# combo.net
KiCad netlist of a schematic drawn in EAGLE
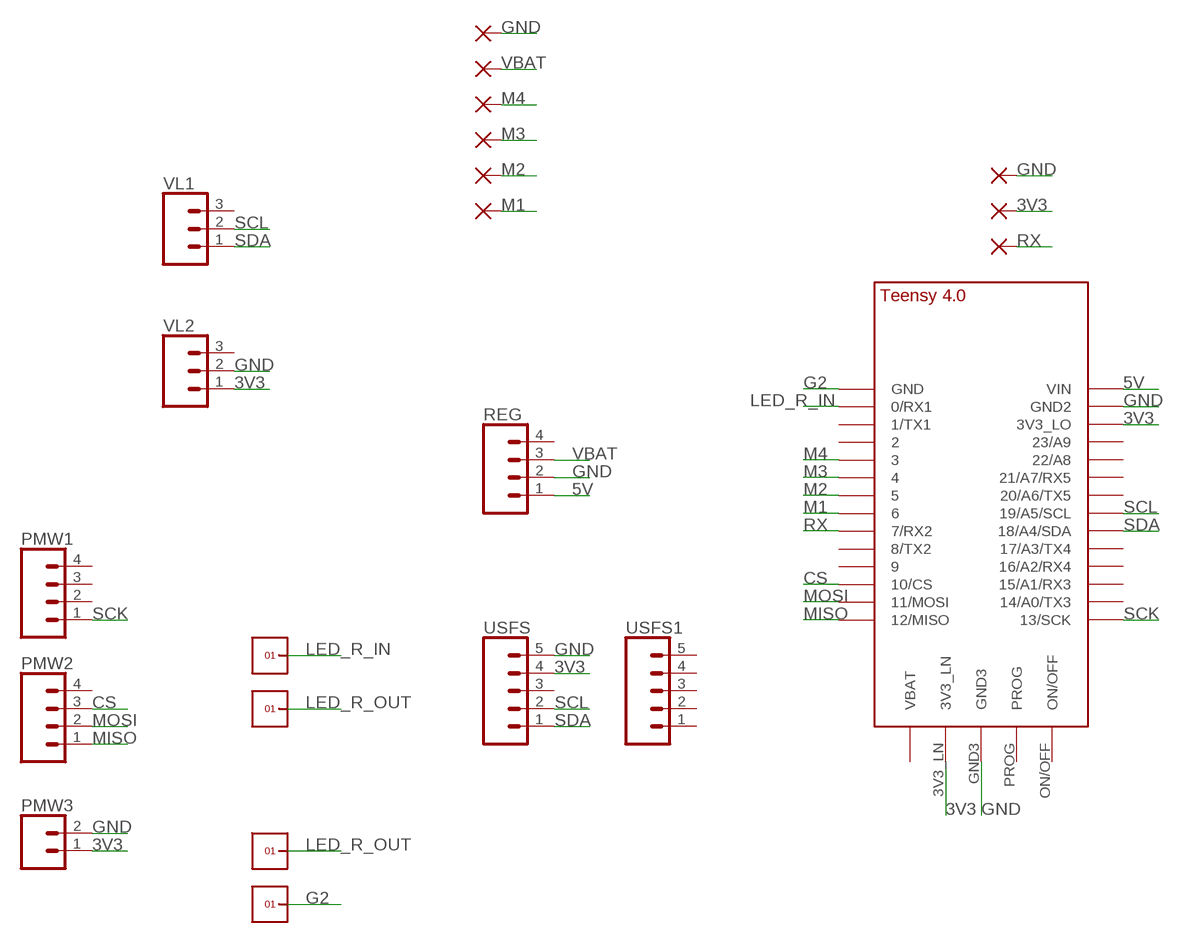
[diagram p0: schematic, sheet 1]

(export (version "E")
  (design (tool "Eeschema 10.0.6"))
  (components
    (comp (ref "3V")
      (value "SMD2")
      (footprint "eagle-import:SMD1,27-2,54")
      (libsource (lib "eagle-import") (part "SMD2"))
    )
    (comp (ref "GD")
      (value "SMD2")
      (footprint "eagle-import:SMD1,27-2,54")
      (libsource (lib "eagle-import") (part "SMD2"))
    )
    (comp (ref "GND")
      (value "SMD2")
      (footprint "eagle-import:SMD1,27-2,54")
      (libsource (lib "eagle-import") (part "SMD2"))
    )
    (comp (ref "M1")
      (value "SMD2")
      (footprint "eagle-import:SMD1,27-2,54")
      (libsource (lib "eagle-import") (part "SMD2"))
    )
    (comp (ref "M2")
      (value "SMD2")
      (footprint "eagle-import:SMD1,27-2,54")
      (libsource (lib "eagle-import") (part "SMD2"))
    )
    (comp (ref "M3")
      (value "SMD2")
      (footprint "eagle-import:SMD1,27-2,54")
      (libsource (lib "eagle-import") (part "SMD2"))
    )
    (comp (ref "M4")
      (value "SMD2")
      (footprint "eagle-import:SMD1,27-2,54")
      (libsource (lib "eagle-import") (part "SMD2"))
    )
    (comp (ref "PMW1")
      (value "CONN_041X04_NO_SILK")
      (footprint "eagle-import:1X04_NO_SILK")
      (libsource (lib "eagle-import") (part "CONN_041X04_NO_SILK"))
    )
    (comp (ref "PMW2")
      (value "CONN_041X04_NO_SILK")
      (footprint "eagle-import:1X04_NO_SILK")
      (libsource (lib "eagle-import") (part "CONN_041X04_NO_SILK"))
    )
    (comp (ref "PMW3")
      (value "CONN_021X02_NO_SILK")
      (footprint "eagle-import:1X02_NO_SILK")
      (libsource (lib "eagle-import") (part "CONN_021X02_NO_SILK"))
    )
    (comp (ref "REG")
      (value "CONN_041X04_NO_SILK")
      (footprint "eagle-import:1X04_NO_SILK")
      (libsource (lib "eagle-import") (part "CONN_041X04_NO_SILK"))
    )
    (comp (ref "RX")
      (value "SMD2")
      (footprint "eagle-import:SMD1,27-2,54")
      (libsource (lib "eagle-import") (part "SMD2"))
    )
    (comp (ref "U$1")
      (value "TEENSY_4.0")
      (footprint "eagle-import:TEENSY_4.0")
      (libsource (lib "eagle-import") (part "TEENSY_4.0"))
    )
    (comp (ref "U$3")
      (value "1X1")
      (footprint "eagle-import:1X1")
      (libsource (lib "eagle-import") (part "1X1"))
    )
    (comp (ref "U$4")
      (value "1X1")
      (footprint "eagle-import:1X1")
      (libsource (lib "eagle-import") (part "1X1"))
    )
    (comp (ref "U$6")
      (value "1X1")
      (footprint "eagle-import:1X1")
      (libsource (lib "eagle-import") (part "1X1"))
    )
    (comp (ref "U$7")
      (value "1X1")
      (footprint "eagle-import:1X1")
      (libsource (lib "eagle-import") (part "1X1"))
    )
    (comp (ref "USFS")
      (value "CONN_05NO_SILK")
      (footprint "eagle-import:1X05_NO_SILK")
      (libsource (lib "eagle-import") (part "CONN_05NO_SILK"))
    )
    (comp (ref "USFS1")
      (value "CONN_05NO_SILK")
      (footprint "eagle-import:1X05_NO_SILK")
      (libsource (lib "eagle-import") (part "CONN_05NO_SILK"))
    )
    (comp (ref "VBAT")
      (value "SMD2")
      (footprint "eagle-import:SMD1,27-2,54")
      (libsource (lib "eagle-import") (part "SMD2"))
    )
    (comp (ref "VL1")
      (value "CONN_031X03_NO_SILK")
      (footprint "eagle-import:1X03_NO_SILK")
      (libsource (lib "eagle-import") (part "CONN_031X03_NO_SILK"))
    )
    (comp (ref "VL2")
      (value "CONN_031X03_NO_SILK")
      (footprint "eagle-import:1X03_NO_SILK")
      (libsource (lib "eagle-import") (part "CONN_031X03_NO_SILK"))
    )
  )
  (nets
    (net (code "1") (name "/3V3") (class "Default")
      (node (ref "3V") (pin "1") (pinfunction "P_1") (pintype "passive"))
      (node (ref "PMW3") (pin "1") (pinfunction "1_1") (pintype "passive"))
      (node (ref "U$1") (pin "3V3_LN") (pinfunction "3V3_LN_3V3_LN") (pintype "bidirectional"))
      (node (ref "U$1") (pin "3V3_LO") (pinfunction "3V3_LO_3V3_LO") (pintype "bidirectional"))
      (node (ref "USFS") (pin "4") (pinfunction "4_4") (pintype "passive"))
      (node (ref "VL2") (pin "1") (pinfunction "1_1") (pintype "passive"))
    )
    (net (code "2") (name "/5V") (class "Default")
      (node (ref "REG") (pin "1") (pinfunction "1_1") (pintype "passive"))
      (node (ref "U$1") (pin "VIN") (pinfunction "VIN_VIN") (pintype "bidirectional"))
    )
    (net (code "3") (name "/CS") (class "Default")
      (node (ref "PMW2") (pin "3") (pinfunction "3_3") (pintype "passive"))
      (node (ref "U$1") (pin "10/CS") (pinfunction "10/CS_10/CS") (pintype "bidirectional"))
    )
    (net (code "4") (name "/G2") (class "Default")
      (node (ref "U$1") (pin "GND") (pinfunction "GND_GND") (pintype "bidirectional"))
      (node (ref "U$7") (pin "1") (pinfunction "1_1") (pintype "bidirectional"))
    )
    (net (code "5") (name "/GND") (class "Default")
      (node (ref "GD") (pin "1") (pinfunction "P_1") (pintype "passive"))
      (node (ref "GND") (pin "1") (pinfunction "P_1") (pintype "passive"))
      (node (ref "PMW3") (pin "2") (pinfunction "2_2") (pintype "passive"))
      (node (ref "REG") (pin "2") (pinfunction "2_2") (pintype "passive"))
      (node (ref "U$1") (pin "GND2") (pinfunction "GND2_GND2") (pintype "bidirectional"))
      (node (ref "U$1") (pin "GND3") (pinfunction "GND3_GND3") (pintype "bidirectional"))
      (node (ref "USFS") (pin "5") (pinfunction "5_5") (pintype "passive"))
      (node (ref "VL2") (pin "2") (pinfunction "2_2") (pintype "passive"))
    )
    (net (code "6") (name "/LED_R_IN") (class "Default")
      (node (ref "U$1") (pin "0/RX") (pinfunction "0/RX1_0/RX") (pintype "bidirectional"))
      (node (ref "U$3") (pin "1") (pinfunction "1_1") (pintype "bidirectional"))
    )
    (net (code "7") (name "/LED_R_OUT") (class "Default")
      (node (ref "U$4") (pin "1") (pinfunction "1_1") (pintype "bidirectional"))
      (node (ref "U$6") (pin "1") (pinfunction "1_1") (pintype "bidirectional"))
    )
    (net (code "8") (name "/M1") (class "Default")
      (node (ref "M1") (pin "1") (pinfunction "P_1") (pintype "passive"))
      (node (ref "U$1") (pin "6") (pinfunction "6_6") (pintype "bidirectional"))
    )
    (net (code "9") (name "/M2") (class "Default")
      (node (ref "M2") (pin "1") (pinfunction "P_1") (pintype "passive"))
      (node (ref "U$1") (pin "5") (pinfunction "5_5") (pintype "bidirectional"))
    )
    (net (code "10") (name "/M3") (class "Default")
      (node (ref "M3") (pin "1") (pinfunction "P_1") (pintype "passive"))
      (node (ref "U$1") (pin "4/CANRX") (pinfunction "4_4/CANRX") (pintype "bidirectional"))
    )
    (net (code "11") (name "/M4") (class "Default")
      (node (ref "M4") (pin "1") (pinfunction "P_1") (pintype "passive"))
      (node (ref "U$1") (pin "3/CANTX") (pinfunction "3_3/CANTX") (pintype "bidirectional"))
    )
    (net (code "12") (name "/MISO") (class "Default")
      (node (ref "PMW2") (pin "1") (pinfunction "1_1") (pintype "passive"))
      (node (ref "U$1") (pin "12/MISO") (pinfunction "12/MISO_12/MISO") (pintype "bidirectional"))
    )
    (net (code "13") (name "/MOSI") (class "Default")
      (node (ref "PMW2") (pin "2") (pinfunction "2_2") (pintype "passive"))
      (node (ref "U$1") (pin "11/MOSI") (pinfunction "11/MOSI_11/MOSI") (pintype "bidirectional"))
    )
    (net (code "14") (name "/RX") (class "Default")
      (node (ref "RX") (pin "1") (pinfunction "P_1") (pintype "passive"))
      (node (ref "U$1") (pin "7") (pinfunction "7/RX2_7") (pintype "bidirectional"))
    )
    (net (code "15") (name "/SCK") (class "Default")
      (node (ref "PMW1") (pin "1") (pinfunction "1_1") (pintype "passive"))
      (node (ref "U$1") (pin "13/SCK") (pinfunction "13/SCK_13/SCK") (pintype "bidirectional"))
    )
    (net (code "16") (name "/SCL") (class "Default")
      (node (ref "U$1") (pin "19/A5/SCL") (pinfunction "19/A5/SCL_19/A5/SCL") (pintype "bidirectional"))
      (node (ref "USFS") (pin "2") (pinfunction "2_2") (pintype "passive"))
      (node (ref "VL1") (pin "2") (pinfunction "2_2") (pintype "passive"))
    )
    (net (code "17") (name "/SDA") (class "Default")
      (node (ref "U$1") (pin "18/A4/SDA") (pinfunction "18/A4/SDA_18/A4/SDA") (pintype "bidirectional"))
      (node (ref "USFS") (pin "1") (pinfunction "1_1") (pintype "passive"))
      (node (ref "VL1") (pin "1") (pinfunction "1_1") (pintype "passive"))
    )
    (net (code "18") (name "/VBAT") (class "Default")
      (node (ref "REG") (pin "3") (pinfunction "3_3") (pintype "passive"))
      (node (ref "VBAT") (pin "1") (pinfunction "P_1") (pintype "passive"))
    )
    (net (code "19") (name "unconnected-(PMW1-Pad2)") (class "Default")
      (node (ref "PMW1") (pin "2") (pinfunction "2_2") (pintype "passive"))
    )
    (net (code "20") (name "unconnected-(PMW1-Pad3)") (class "Default")
      (node (ref "PMW1") (pin "3") (pinfunction "3_3") (pintype "passive"))
    )
    (net (code "21") (name "unconnected-(PMW1-Pad4)") (class "Default")
      (node (ref "PMW1") (pin "4") (pinfunction "4_4") (pintype "passive"))
    )
    (net (code "22") (name "unconnected-(PMW2-Pad4)") (class "Default")
      (node (ref "PMW2") (pin "4") (pinfunction "4_4") (pintype "passive"))
    )
    (net (code "23") (name "unconnected-(REG-Pad4)") (class "Default")
      (node (ref "REG") (pin "4") (pinfunction "4_4") (pintype "passive"))
    )
    (net (code "24") (name "unconnected-(U$1-1{slash}TX1-Pad1{slash}TX)") (class "Default")
      (node (ref "U$1") (pin "1/TX") (pinfunction "1/TX1_1/TX") (pintype "bidirectional"))
    )
    (net (code "25") (name "unconnected-(U$1-8{slash}TX2-Pad8)") (class "Default")
      (node (ref "U$1") (pin "8") (pinfunction "8/TX2_8") (pintype "bidirectional"))
    )
    (net (code "26") (name "unconnected-(U$1-9-Pad9{slash}CS)") (class "Default")
      (node (ref "U$1") (pin "9/CS") (pinfunction "9_9/CS") (pintype "bidirectional"))
    )
    (net (code "27") (name "unconnected-(U$1-14{slash}A0{slash}TX3-Pad14{slash}A0)") (class "Default")
      (node (ref "U$1") (pin "14/A0") (pinfunction "14/A0/TX3_14/A0") (pintype "bidirectional"))
    )
    (net (code "28") (name "unconnected-(U$1-15{slash}A1{slash}RX3-Pad15{slash}A1)") (class "Default")
      (node (ref "U$1") (pin "15/A1") (pinfunction "15/A1/RX3_15/A1") (pintype "bidirectional"))
    )
    (net (code "29") (name "unconnected-(U$1-16{slash}A2{slash}RX4-Pad16{slash}A2)") (class "Default")
      (node (ref "U$1") (pin "16/A2") (pinfunction "16/A2/RX4_16/A2") (pintype "bidirectional"))
    )
    (net (code "30") (name "unconnected-(U$1-17{slash}A3{slash}TX4-Pad17{slash}A3)") (class "Default")
      (node (ref "U$1") (pin "17/A3") (pinfunction "17/A3/TX4_17/A3") (pintype "bidirectional"))
    )
    (net (code "31") (name "unconnected-(U$1-20{slash}A6{slash}TX5-Pad20{slash}A6)") (class "Default")
      (node (ref "U$1") (pin "20/A6") (pinfunction "20/A6/TX5_20/A6") (pintype "bidirectional"))
    )
    (net (code "32") (name "unconnected-(U$1-21{slash}A7{slash}RX5-Pad21{slash}A7)") (class "Default")
      (node (ref "U$1") (pin "21/A7") (pinfunction "21/A7/RX5_21/A7") (pintype "bidirectional"))
    )
    (net (code "33") (name "unconnected-(U$1-Pad2)") (class "Default")
      (node (ref "U$1") (pin "2") (pinfunction "2_2") (pintype "bidirectional"))
    )
    (net (code "34") (name "unconnected-(U$1-Pad22{slash}A8)") (class "Default")
      (node (ref "U$1") (pin "22/A8") (pinfunction "22/A8_22/A8") (pintype "bidirectional"))
    )
    (net (code "35") (name "unconnected-(U$1-Pad23{slash}A9)") (class "Default")
      (node (ref "U$1") (pin "23/A9") (pinfunction "23/A9_23/A9") (pintype "bidirectional"))
    )
    (net (code "36") (name "unconnected-(U$1-PadON{slash}OFF)") (class "Default")
      (node (ref "U$1") (pin "ON/OFF") (pinfunction "ON/OFF_ON/OFF") (pintype "bidirectional"))
    )
    (net (code "37") (name "unconnected-(U$1-PadPROG)") (class "Default")
      (node (ref "U$1") (pin "PROG") (pinfunction "PROG_PROG") (pintype "bidirectional"))
    )
    (net (code "38") (name "unconnected-(U$1-VBAT-PadVBAT\\)") (class "Default")
      (node (ref "U$1") (pin "VBAT\\") (pinfunction "VBAT_VBAT\\") (pintype "bidirectional"))
    )
    (net (code "39") (name "unconnected-(USFS-Pad3)") (class "Default")
      (node (ref "USFS") (pin "3") (pinfunction "3_3") (pintype "passive"))
    )
    (net (code "40") (name "unconnected-(USFS1-Pad1)") (class "Default")
      (node (ref "USFS1") (pin "1") (pinfunction "1_1") (pintype "passive"))
    )
    (net (code "41") (name "unconnected-(USFS1-Pad2)") (class "Default")
      (node (ref "USFS1") (pin "2") (pinfunction "2_2") (pintype "passive"))
    )
    (net (code "42") (name "unconnected-(USFS1-Pad3)") (class "Default")
      (node (ref "USFS1") (pin "3") (pinfunction "3_3") (pintype "passive"))
    )
    (net (code "43") (name "unconnected-(USFS1-Pad4)") (class "Default")
      (node (ref "USFS1") (pin "4") (pinfunction "4_4") (pintype "passive"))
    )
    (net (code "44") (name "unconnected-(USFS1-Pad5)") (class "Default")
      (node (ref "USFS1") (pin "5") (pinfunction "5_5") (pintype "passive"))
    )
    (net (code "45") (name "unconnected-(VL1-Pad3)") (class "Default")
      (node (ref "VL1") (pin "3") (pinfunction "3_3") (pintype "passive"))
    )
    (net (code "46") (name "unconnected-(VL2-Pad3)") (class "Default")
      (node (ref "VL2") (pin "3") (pinfunction "3_3") (pintype "passive"))
    )
  )
)
